# FSR-Sensor.net
KiCad netlist of a schematic drawn in EAGLE
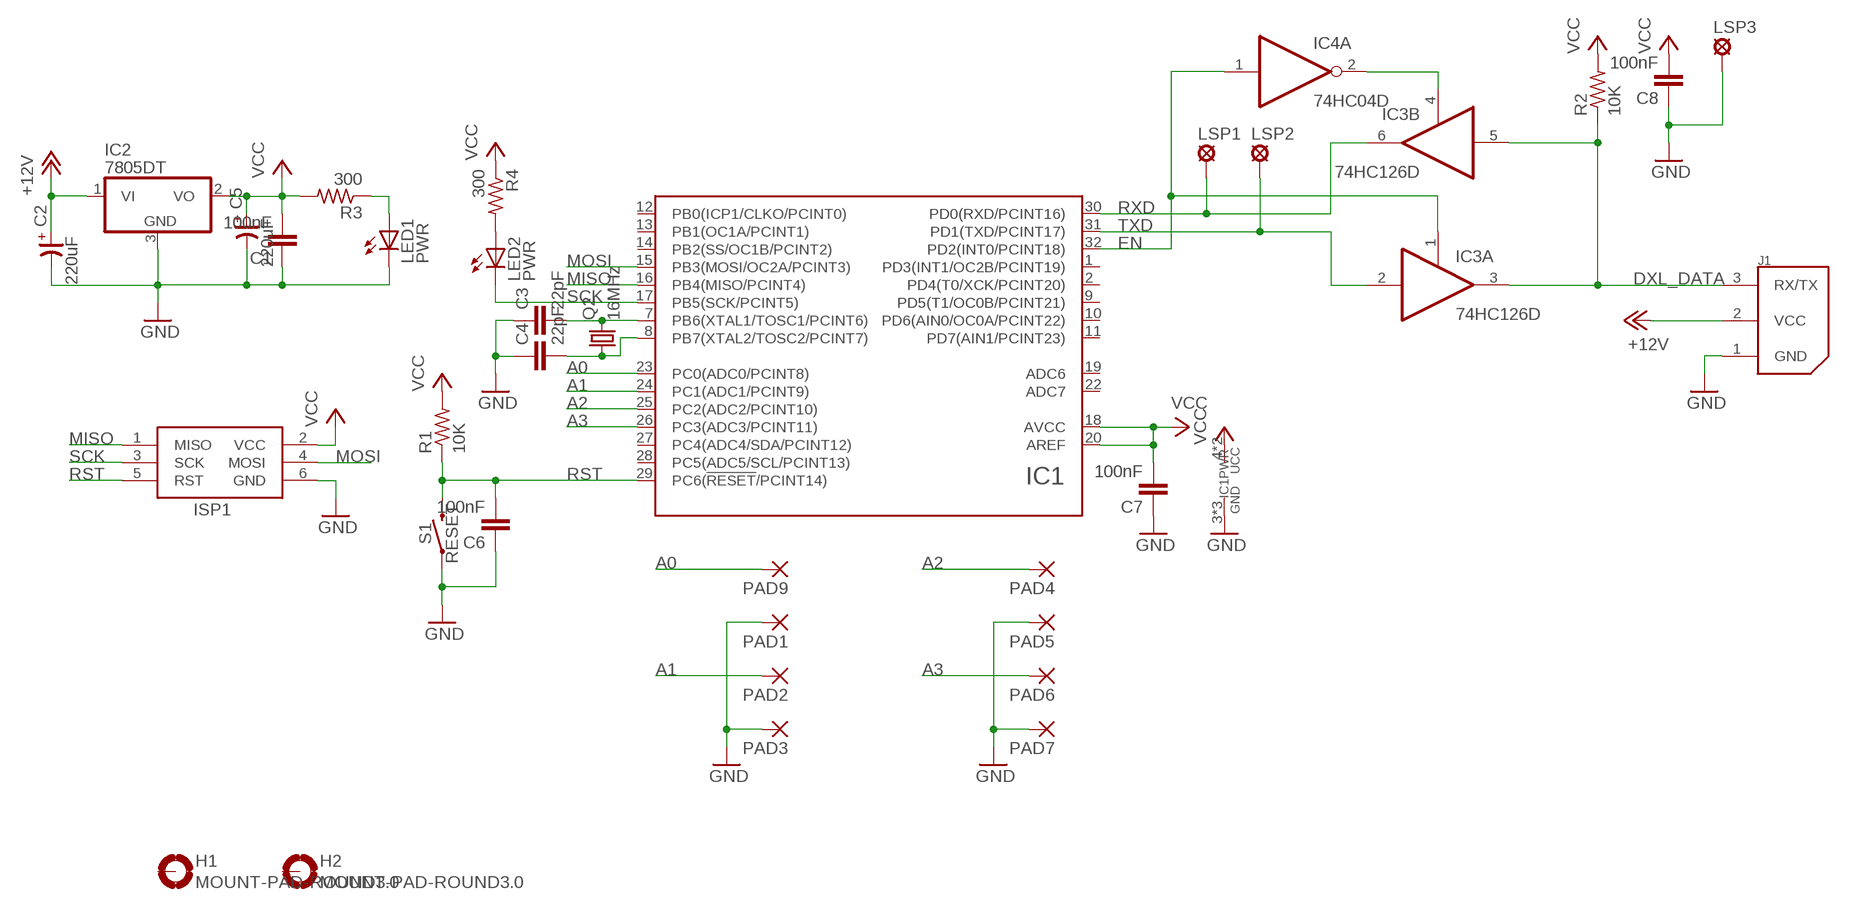
[diagram p0: schematic, sheet 1]

(export (version "E")
  (design (tool "Eeschema 10.0.6"))
  (components
    (comp (ref "C1")
      (value "100nF")
      (footprint "eagle-import:C0805K")
      (libsource (lib "eagle-import") (part "C-EUC0805K"))
    )
    (comp (ref "C2")
      (value "220uF")
      (footprint "eagle-import:7343_T")
      (libsource (lib "eagle-import") (part "CP-7343"))
    )
    (comp (ref "C3")
      (value "22pF")
      (footprint "eagle-import:C0805K")
      (libsource (lib "eagle-import") (part "C-EUC0805K"))
    )
    (comp (ref "C4")
      (value "22pF")
      (footprint "eagle-import:C0805K")
      (libsource (lib "eagle-import") (part "C-EUC0805K"))
    )
    (comp (ref "C5")
      (value "220uF")
      (footprint "eagle-import:7343_T")
      (libsource (lib "eagle-import") (part "CP-7343"))
    )
    (comp (ref "C6")
      (value "100nF")
      (footprint "eagle-import:C0805K")
      (libsource (lib "eagle-import") (part "C-EUC0805K"))
    )
    (comp (ref "C7")
      (value "100nF")
      (footprint "eagle-import:C0805K")
      (libsource (lib "eagle-import") (part "C-EUC0805K"))
    )
    (comp (ref "C8")
      (value "100nF")
      (footprint "eagle-import:C0805K")
      (libsource (lib "eagle-import") (part "C-EUC0805K"))
    )
    (comp (ref "H1")
      (value "MOUNT-PAD-ROUND3.0")
      (footprint "eagle-import:3,0-PAD")
      (libsource (lib "eagle-import") (part "MOUNT-PAD-ROUND3.0"))
    )
    (comp (ref "H2")
      (value "MOUNT-PAD-ROUND3.0")
      (footprint "eagle-import:3,0-PAD")
      (libsource (lib "eagle-import") (part "MOUNT-PAD-ROUND3.0"))
    )
    (comp (ref "IC1")
      (value "ATMEGA48/88/168/328-AU")
      (footprint "eagle-import:TQFP32-08")
      (libsource (lib "eagle-import") (part "ATMEGA48/88/168/328-AU"))
    )
    (comp (ref "IC2")
      (value "7805DT")
      (footprint "eagle-import:TO252")
      (libsource (lib "eagle-import") (part "78DT05"))
    )
    (comp (ref "IC3")
      (value "74HC126D")
      (footprint "eagle-import:SO14")
      (libsource (lib "eagle-import") (part "74126DHC"))
    )
    (comp (ref "IC4")
      (value "74HC04D")
      (footprint "eagle-import:SO14")
      (libsource (lib "eagle-import") (part "7404DHC"))
    )
    (comp (ref "ISP1")
      (value "AVRISP-6")
      (footprint "eagle-import:AVRISP")
      (libsource (lib "eagle-import") (part "AVRISP-6"))
    )
    (comp (ref "J1")
      (value "22-03-5035")
      (footprint "eagle-import:5267-3")
      (libsource (lib "eagle-import") (part "22-03-5035"))
    )
    (comp (ref "LED1")
      (value "PWR")
      (footprint "eagle-import:CHIP-LED0805")
      (libsource (lib "eagle-import") (part "LEDCHIP-LED0805"))
    )
    (comp (ref "LED2")
      (value "PWR")
      (footprint "eagle-import:CHIP-LED0805")
      (libsource (lib "eagle-import") (part "LEDCHIP-LED0805"))
    )
    (comp (ref "LSP1")
      (value "LSP10")
      (footprint "eagle-import:LSP10")
      (libsource (lib "eagle-import") (part "LSP10"))
    )
    (comp (ref "LSP2")
      (value "LSP10")
      (footprint "eagle-import:LSP10")
      (libsource (lib "eagle-import") (part "LSP10"))
    )
    (comp (ref "LSP3")
      (value "LSP10")
      (footprint "eagle-import:LSP10")
      (libsource (lib "eagle-import") (part "LSP10"))
    )
    (comp (ref "PAD1")
      (value "SMD2")
      (footprint "eagle-import:SMD1,27-2,54")
      (libsource (lib "eagle-import") (part "SMD2"))
    )
    (comp (ref "PAD2")
      (value "SMD2")
      (footprint "eagle-import:SMD1,27-2,54")
      (libsource (lib "eagle-import") (part "SMD2"))
    )
    (comp (ref "PAD3")
      (value "SMD2")
      (footprint "eagle-import:SMD1,27-2,54")
      (libsource (lib "eagle-import") (part "SMD2"))
    )
    (comp (ref "PAD4")
      (value "SMD2")
      (footprint "eagle-import:SMD1,27-2,54")
      (libsource (lib "eagle-import") (part "SMD2"))
    )
    (comp (ref "PAD5")
      (value "SMD2")
      (footprint "eagle-import:SMD1,27-2,54")
      (libsource (lib "eagle-import") (part "SMD2"))
    )
    (comp (ref "PAD6")
      (value "SMD2")
      (footprint "eagle-import:SMD1,27-2,54")
      (libsource (lib "eagle-import") (part "SMD2"))
    )
    (comp (ref "PAD7")
      (value "SMD2")
      (footprint "eagle-import:SMD1,27-2,54")
      (libsource (lib "eagle-import") (part "SMD2"))
    )
    (comp (ref "PAD9")
      (value "SMD2")
      (footprint "eagle-import:SMD1,27-2,54")
      (libsource (lib "eagle-import") (part "SMD2"))
    )
    (comp (ref "Q2")
      (value "16MHz")
      (footprint "eagle-import:HC49UP")
      (libsource (lib "eagle-import") (part "CRYSTALHC49UP"))
    )
    (comp (ref "R1")
      (value "10K")
      (footprint "eagle-import:R0805")
      (libsource (lib "eagle-import") (part "R-US_R0805"))
    )
    (comp (ref "R2")
      (value "10K")
      (footprint "eagle-import:R0805")
      (libsource (lib "eagle-import") (part "R-US_R0805"))
    )
    (comp (ref "R3")
      (value "300")
      (footprint "eagle-import:R0805")
      (libsource (lib "eagle-import") (part "R-US_R0805"))
    )
    (comp (ref "R4")
      (value "300")
      (footprint "eagle-import:R0805")
      (libsource (lib "eagle-import") (part "R-US_R0805"))
    )
    (comp (ref "S1")
      (value "RESET")
      (footprint "eagle-import:TACTILE_SWITCH_SMD_6.0X3.5MM")
      (libsource (lib "eagle-import") (part "MOMENTARY-SWITCH-SPST-SMD-6.0X3.5MM"))
    )
  )
  (nets
    (net (code "1") (name "+12V") (class "Default")
      (node (ref "C2") (pin "+") (pinfunction "+_+") (pintype "passive"))
      (node (ref "IC2") (pin "1") (pinfunction "VI_1") (pintype "input"))
      (node (ref "J1") (pin "2") (pinfunction "VCC_2") (pintype "bidirectional"))
    )
    (net (code "2") (name "/A0") (class "Default")
      (node (ref "IC1") (pin "23") (pinfunction "PC0(ADC0/PCINT8)_23") (pintype "bidirectional"))
      (node (ref "PAD9") (pin "1") (pinfunction "P_1") (pintype "passive"))
    )
    (net (code "3") (name "/A1") (class "Default")
      (node (ref "IC1") (pin "24") (pinfunction "PC1(ADC1/PCINT9)_24") (pintype "bidirectional"))
      (node (ref "PAD2") (pin "1") (pinfunction "P_1") (pintype "passive"))
    )
    (net (code "4") (name "/A2") (class "Default")
      (node (ref "IC1") (pin "25") (pinfunction "PC2(ADC2/PCINT10)_25") (pintype "bidirectional"))
      (node (ref "PAD4") (pin "1") (pinfunction "P_1") (pintype "passive"))
    )
    (net (code "5") (name "/A3") (class "Default")
      (node (ref "IC1") (pin "26") (pinfunction "PC3(ADC3/PCINT11)_26") (pintype "bidirectional"))
      (node (ref "PAD6") (pin "1") (pinfunction "P_1") (pintype "passive"))
    )
    (net (code "6") (name "/DXL_DATA") (class "Default")
      (node (ref "IC3") (pin "3") (pinfunction "O_3") (pintype "output"))
      (node (ref "IC3") (pin "5") (pinfunction "I_5") (pintype "input"))
      (node (ref "J1") (pin "3") (pinfunction "RX/TX_3") (pintype "bidirectional"))
      (node (ref "R2") (pin "1") (pinfunction "1_1") (pintype "passive"))
    )
    (net (code "7") (name "/EN") (class "Default")
      (node (ref "IC1") (pin "32") (pinfunction "PD2(INT0/PCINT18)_32") (pintype "bidirectional"))
      (node (ref "IC3") (pin "1") (pinfunction "OE_1") (pintype "input"))
      (node (ref "IC4") (pin "1") (pinfunction "I_1") (pintype "input"))
    )
    (net (code "8") (name "/MISO") (class "Default")
      (node (ref "IC1") (pin "16") (pinfunction "PB4(MISO/PCINT4)_16") (pintype "bidirectional"))
      (node (ref "ISP1") (pin "1") (pinfunction "MISO_1") (pintype "input"))
    )
    (net (code "9") (name "/MOSI") (class "Default")
      (node (ref "IC1") (pin "15") (pinfunction "PB3(MOSI/OC2A/PCINT3)_15") (pintype "bidirectional"))
      (node (ref "ISP1") (pin "4") (pinfunction "MOSI_4") (pintype "output"))
    )
    (net (code "10") (name "/RST") (class "Default")
      (node (ref "C6") (pin "2") (pinfunction "2_2") (pintype "passive"))
      (node (ref "IC1") (pin "29") (pinfunction "PC6(~{RESET}/PCINT14)_29") (pintype "bidirectional"))
      (node (ref "ISP1") (pin "5") (pinfunction "RST_5") (pintype "output"))
      (node (ref "R1") (pin "1") (pinfunction "1_1") (pintype "passive"))
      (node (ref "S1") (pin "2") (pinfunction "2_2") (pintype "passive"))
    )
    (net (code "11") (name "/RXD") (class "Default")
      (node (ref "IC1") (pin "30") (pinfunction "PD0(RXD/PCINT16)_30") (pintype "bidirectional"))
      (node (ref "IC3") (pin "6") (pinfunction "O_6") (pintype "output"))
      (node (ref "LSP1") (pin "MP") (pinfunction "MP_MP") (pintype "passive"))
    )
    (net (code "12") (name "/SCK") (class "Default")
      (node (ref "IC1") (pin "17") (pinfunction "PB5(SCK/PCINT5)_17") (pintype "bidirectional"))
      (node (ref "ISP1") (pin "3") (pinfunction "SCK_3") (pintype "output"))
      (node (ref "LED2") (pin "C") (pinfunction "C_C") (pintype "passive"))
    )
    (net (code "13") (name "/TXD") (class "Default")
      (node (ref "IC1") (pin "31") (pinfunction "PD1(TXD/PCINT17)_31") (pintype "bidirectional"))
      (node (ref "IC3") (pin "2") (pinfunction "I_2") (pintype "input"))
      (node (ref "LSP2") (pin "MP") (pinfunction "MP_MP") (pintype "passive"))
    )
    (net (code "14") (name "GND") (class "Default")
      (node (ref "C1") (pin "1") (pinfunction "1_1") (pintype "passive"))
      (node (ref "C2") (pin "-") (pinfunction "-_-") (pintype "passive"))
      (node (ref "C3") (pin "1") (pinfunction "1_1") (pintype "passive"))
      (node (ref "C4") (pin "1") (pinfunction "1_1") (pintype "passive"))
      (node (ref "C5") (pin "-") (pinfunction "-_-") (pintype "passive"))
      (node (ref "C6") (pin "1") (pinfunction "1_1") (pintype "passive"))
      (node (ref "C7") (pin "1") (pinfunction "1_1") (pintype "passive"))
      (node (ref "C8") (pin "1") (pinfunction "1_1") (pintype "passive"))
      (node (ref "IC1") (pin "21") (pinfunction "GND_21") (pintype "power_in"))
      (node (ref "IC1") (pin "3") (pinfunction "GND_3") (pintype "power_in"))
      (node (ref "IC1") (pin "5") (pinfunction "GND_5") (pintype "power_in"))
      (node (ref "IC2") (pin "3") (pinfunction "GND_3") (pintype "passive"))
      (node (ref "ISP1") (pin "6") (pinfunction "GND_6") (pintype "power_in"))
      (node (ref "J1") (pin "1") (pinfunction "GND_1") (pintype "bidirectional"))
      (node (ref "LED1") (pin "C") (pinfunction "C_C") (pintype "passive"))
      (node (ref "LSP3") (pin "MP") (pinfunction "MP_MP") (pintype "passive"))
      (node (ref "PAD1") (pin "1") (pinfunction "P_1") (pintype "passive"))
      (node (ref "PAD3") (pin "1") (pinfunction "P_1") (pintype "passive"))
      (node (ref "PAD5") (pin "1") (pinfunction "P_1") (pintype "passive"))
      (node (ref "PAD7") (pin "1") (pinfunction "P_1") (pintype "passive"))
      (node (ref "S1") (pin "1") (pinfunction "1_1") (pintype "passive"))
    )
    (net (code "15") (name "Net-(IC1A-PB6(XTAL1{slash}TOSC1{slash}PCINT6))") (class "Default")
      (node (ref "C3") (pin "2") (pinfunction "2_2") (pintype "passive"))
      (node (ref "IC1") (pin "7") (pinfunction "PB6(XTAL1/TOSC1/PCINT6)_7") (pintype "bidirectional"))
      (node (ref "Q2") (pin "2") (pinfunction "2_2") (pintype "passive"))
    )
    (net (code "16") (name "Net-(IC1A-PB7(XTAL2{slash}TOSC2{slash}PCINT7))") (class "Default")
      (node (ref "C4") (pin "2") (pinfunction "2_2") (pintype "passive"))
      (node (ref "IC1") (pin "8") (pinfunction "PB7(XTAL2/TOSC2/PCINT7)_8") (pintype "bidirectional"))
      (node (ref "Q2") (pin "1") (pinfunction "1_1") (pintype "passive"))
    )
    (net (code "17") (name "Net-(IC3B-OE)") (class "Default")
      (node (ref "IC3") (pin "4") (pinfunction "OE_4") (pintype "input"))
      (node (ref "IC4") (pin "2") (pinfunction "O_2") (pintype "output"))
    )
    (net (code "18") (name "Net-(LED1-PadA)") (class "Default")
      (node (ref "LED1") (pin "A") (pinfunction "A_A") (pintype "passive"))
      (node (ref "R3") (pin "1") (pinfunction "1_1") (pintype "passive"))
    )
    (net (code "19") (name "Net-(LED2-PadA)") (class "Default")
      (node (ref "LED2") (pin "A") (pinfunction "A_A") (pintype "passive"))
      (node (ref "R4") (pin "2") (pinfunction "2_2") (pintype "passive"))
    )
    (net (code "20") (name "VCC") (class "Default")
      (node (ref "C1") (pin "2") (pinfunction "2_2") (pintype "passive"))
      (node (ref "C5") (pin "+") (pinfunction "+_+") (pintype "passive"))
      (node (ref "C7") (pin "2") (pinfunction "2_2") (pintype "passive"))
      (node (ref "C8") (pin "2") (pinfunction "2_2") (pintype "passive"))
      (node (ref "IC1") (pin "18") (pinfunction "AVCC_18") (pintype "power_in"))
      (node (ref "IC1") (pin "20") (pinfunction "AREF_20") (pintype "passive"))
      (node (ref "IC1") (pin "4") (pinfunction "UCC_4") (pintype "power_in"))
      (node (ref "IC1") (pin "6") (pinfunction "UCC_6") (pintype "power_in"))
      (node (ref "IC2") (pin "2") (pinfunction "VO_2") (pintype "passive"))
      (node (ref "ISP1") (pin "2") (pinfunction "VCC_2") (pintype "power_in"))
      (node (ref "R1") (pin "2") (pinfunction "2_2") (pintype "passive"))
      (node (ref "R2") (pin "2") (pinfunction "2_2") (pintype "passive"))
      (node (ref "R3") (pin "2") (pinfunction "2_2") (pintype "passive"))
      (node (ref "R4") (pin "1") (pinfunction "1_1") (pintype "passive"))
    )
    (net (code "21") (name "unconnected-(H1-MOUNT-PadB3,0)") (class "Default")
      (node (ref "H1") (pin "B3,0") (pinfunction "MOUNT_B3,0") (pintype "passive"))
    )
    (net (code "22") (name "unconnected-(H2-MOUNT-PadB3,0)") (class "Default")
      (node (ref "H2") (pin "B3,0") (pinfunction "MOUNT_B3,0") (pintype "passive"))
    )
    (net (code "23") (name "unconnected-(IC1A-ADC6-Pad19)") (class "Default")
      (node (ref "IC1") (pin "19") (pinfunction "ADC6_19") (pintype "passive"))
    )
    (net (code "24") (name "unconnected-(IC1A-ADC7-Pad22)") (class "Default")
      (node (ref "IC1") (pin "22") (pinfunction "ADC7_22") (pintype "passive"))
    )
    (net (code "25") (name "unconnected-(IC1A-PB0(ICP1{slash}CLKO{slash}PCINT0)-Pad12)") (class "Default")
      (node (ref "IC1") (pin "12") (pinfunction "PB0(ICP1/CLKO/PCINT0)_12") (pintype "bidirectional"))
    )
    (net (code "26") (name "unconnected-(IC1A-PB1(OC1A{slash}PCINT1)-Pad13)") (class "Default")
      (node (ref "IC1") (pin "13") (pinfunction "PB1(OC1A/PCINT1)_13") (pintype "bidirectional"))
    )
    (net (code "27") (name "unconnected-(IC1A-PB2(SS{slash}OC1B{slash}PCINT2)-Pad14)") (class "Default")
      (node (ref "IC1") (pin "14") (pinfunction "PB2(SS/OC1B/PCINT2)_14") (pintype "bidirectional"))
    )
    (net (code "28") (name "unconnected-(IC1A-PC4(ADC4{slash}SDA{slash}PCINT12)-Pad27)") (class "Default")
      (node (ref "IC1") (pin "27") (pinfunction "PC4(ADC4/SDA/PCINT12)_27") (pintype "bidirectional"))
    )
    (net (code "29") (name "unconnected-(IC1A-PC5(ADC5{slash}SCL{slash}PCINT13)-Pad28)") (class "Default")
      (node (ref "IC1") (pin "28") (pinfunction "PC5(ADC5/SCL/PCINT13)_28") (pintype "bidirectional"))
    )
    (net (code "30") (name "unconnected-(IC1A-PD3(INT1{slash}OC2B{slash}PCINT19)-Pad1)") (class "Default")
      (node (ref "IC1") (pin "1") (pinfunction "PD3(INT1/OC2B/PCINT19)_1") (pintype "bidirectional"))
    )
    (net (code "31") (name "unconnected-(IC1A-PD4(T0{slash}XCK{slash}PCINT20)-Pad2)") (class "Default")
      (node (ref "IC1") (pin "2") (pinfunction "PD4(T0/XCK/PCINT20)_2") (pintype "bidirectional"))
    )
    (net (code "32") (name "unconnected-(IC1A-PD5(T1{slash}OC0B{slash}PCINT21)-Pad9)") (class "Default")
      (node (ref "IC1") (pin "9") (pinfunction "PD5(T1/OC0B/PCINT21)_9") (pintype "bidirectional"))
    )
    (net (code "33") (name "unconnected-(IC1A-PD6(AIN0{slash}OC0A{slash}PCINT22)-Pad10)") (class "Default")
      (node (ref "IC1") (pin "10") (pinfunction "PD6(AIN0/OC0A/PCINT22)_10") (pintype "bidirectional"))
    )
    (net (code "34") (name "unconnected-(IC1A-PD7(AIN1{slash}PCINT23)-Pad11)") (class "Default")
      (node (ref "IC1") (pin "11") (pinfunction "PD7(AIN1/PCINT23)_11") (pintype "bidirectional"))
    )
  )
)
